# Arduino_Core.net
KiCad netlist of a schematic drawn in Altium Designer
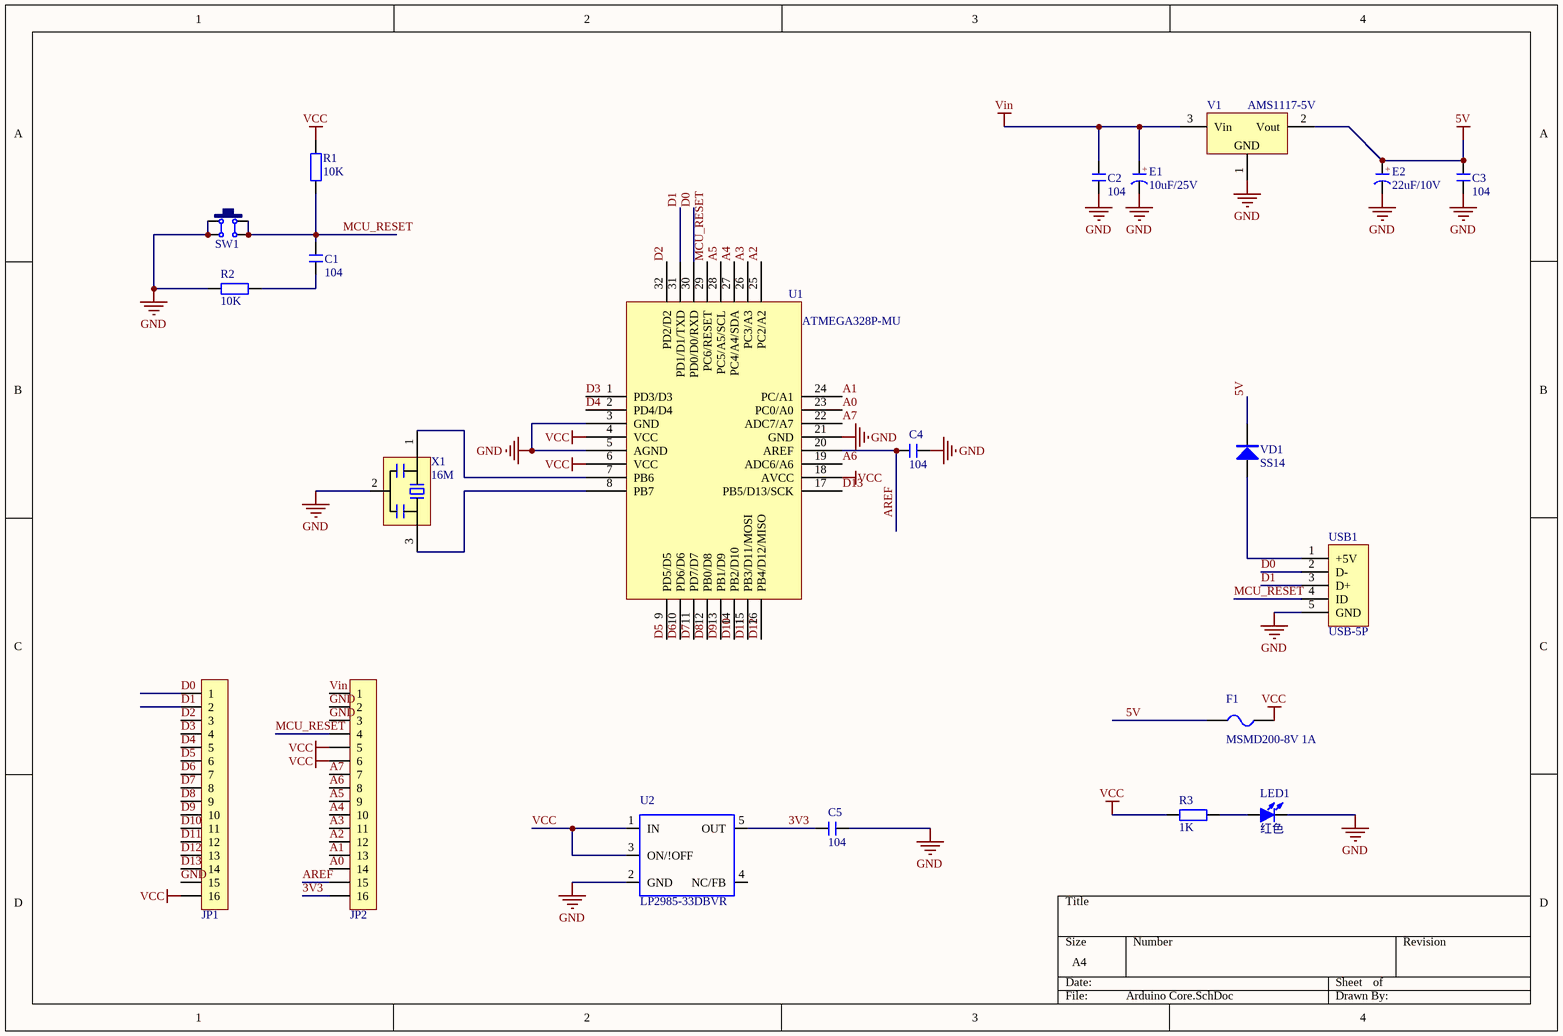
[diagram p0: Arduino Core.SchDoc]

(export (version "E")
  (design (tool "Eeschema 10.0.6"))
  (components
    (comp (ref "C1")
      (value "104")
      (footprint "C 0603")
      (description "无极性贴片电容")
      (fields (field (name "版权归属") "源创客"))
      (libsource (lib "电阻-电容-电感") (part "C"))
    )
    (comp (ref "C2")
      (value "104")
      (footprint "C 0603")
      (description "无极性贴片电容")
      (fields (field (name "版权归属") "源创客"))
      (libsource (lib "电阻-电容-电感") (part "C"))
    )
    (comp (ref "C3")
      (value "104")
      (footprint "C 0603")
      (description "无极性贴片电容")
      (fields (field (name "版权归属") "源创客"))
      (libsource (lib "电阻-电容-电感") (part "C"))
    )
    (comp (ref "C4")
      (value "104")
      (footprint "C 0603")
      (description "无极性贴片电容")
      (fields (field (name "版权归属") "源创客"))
      (libsource (lib "电阻-电容-电感") (part "C"))
    )
    (comp (ref "C5")
      (value "104")
      (footprint "C 0603")
      (description "无极性贴片电容")
      (fields (field (name "版权归属") "源创客"))
      (libsource (lib "电阻-电容-电感") (part "C"))
    )
    (comp (ref "E1")
      (value "10uF/25V")
      (footprint "CD A(3216)")
      (description "贴片钽电容")
      (fields (field (name "版权归属") "源创客"))
      (libsource (lib "电阻-电容-电感") (part "C-CD"))
    )
    (comp (ref "E2")
      (value "22uF/10V")
      (footprint "CD A(3216)")
      (description "贴片钽电容")
      (fields (field (name "版权归属") "源创客"))
      (libsource (lib "电阻-电容-电感") (part "C-CD"))
    )
    (comp (ref "F1")
      (value "MSMD200-8V 1A")
      (footprint "FU 1812")
      (description "贴片保险丝")
      (fields (field (name "版权归属") "源创客"))
      (libsource (lib "保险丝-晶振") (part "FU"))
    )
    (comp (ref "JP1")
      (value "HDR-1X16")
      (footprint "HDR-1X16")
      (description "16P接插件")
      (fields (field (name "版权归属") "源创客"))
      (libsource (lib "接插件") (part "Header 16"))
    )
    (comp (ref "JP2")
      (value "HDR-1X16")
      (footprint "HDR-1X16")
      (description "16P接插件")
      (fields (field (name "版权归属") "源创客"))
      (libsource (lib "接插件") (part "Header 16"))
    )
    (comp (ref "LED1")
      (value "红色")
      (footprint "LED 0603B")
      (description "贴片LED")
      (fields (field (name "版权归属") "源创客"))
      (libsource (lib "LED") (part "LED-SMD"))
    )
    (comp (ref "R1")
      (value "10K")
      (footprint "R 0603")
      (description "贴片电阻")
      (fields (field (name "版权归属") "源创客"))
      (libsource (lib "电阻-电容-电感") (part "R"))
    )
    (comp (ref "R2")
      (value "10K")
      (footprint "R 0603")
      (description "贴片电阻")
      (fields (field (name "版权归属") "源创客"))
      (libsource (lib "电阻-电容-电感") (part "R"))
    )
    (comp (ref "R3")
      (value "1K")
      (footprint "R 0603")
      (description "贴片电阻")
      (fields (field (name "版权归属") "源创客"))
      (libsource (lib "电阻-电容-电感") (part "R"))
    )
    (comp (ref "SW1")
      (value "4x4x1.5")
      (footprint "TS4x4x1.5")
      (description "防水轻触开关")
      (fields (field (name "版权归属") "源创客"))
      (libsource (lib "5.1   - 按键-开关") (part "TS-030"))
    )
    (comp (ref "U1")
      (value "ATMEGA328P-MU")
      (footprint "LQFP32 7X7_L")
      (description "AVR单片机")
      (fields (field (name "版权归属") "源创客"))
      (libsource (lib "Atmel系列单片机") (part "ATMEGA328P"))
    )
    (comp (ref "U2")
      (value "LP2985-33DBVR")
      (footprint "SOT23-5L")
      (libsource (lib "*") (part "LP2985-XXDBVR33"))
    )
    (comp (ref "USB1")
      (value "USB-5P")
      (footprint "USB-MICRO_D")
      (description "微型USB母座")
      (fields (field (name "版权归属") "源创客"))
      (libsource (lib "接口类") (part "USB-5P"))
    )
    (comp (ref "V1")
      (value "AMS1117-5V")
      (footprint "SOT223_N")
      (description "三端稳压芯片")
      (fields (field (name "版权归属") "源创客"))
      (libsource (lib "IC芯片") (part "AMS1117"))
    )
    (comp (ref "VD1")
      (value "SS14")
      (footprint "SMA")
      (description "肖特基二极管")
      (fields (field (name "版权归属") "源创客"))
      (libsource (lib "二极管-整流桥") (part "SS14"))
    )
    (comp (ref "X1")
      (value "16M")
      (footprint "T-3213")
      (description "3脚晶振")
      (fields (field (name "版权归属") "源创客"))
      (libsource (lib "保险丝-晶振") (part "XTAL-3"))
    )
  )
  (nets
    (net (code "1") (name "/3V3") (class "Default")
      (node (ref "C5") (pin "1") (pinfunction "1_1") (pintype "passive"))
      (node (ref "JP2") (pin "16") (pinfunction "16_16") (pintype "passive"))
      (node (ref "U2") (pin "5") (pinfunction "OUT_5") (pintype "passive"))
    )
    (net (code "2") (name "/A0") (class "Default")
      (node (ref "JP2") (pin "14") (pinfunction "14_14") (pintype "passive"))
      (node (ref "U1") (pin "23") (pinfunction "PC0/A0_23") (pintype "passive"))
    )
    (net (code "3") (name "/A1") (class "Default")
      (node (ref "JP2") (pin "13") (pinfunction "13_13") (pintype "passive"))
      (node (ref "U1") (pin "24") (pinfunction "PC/A1_24") (pintype "passive"))
    )
    (net (code "4") (name "/A2") (class "Default")
      (node (ref "JP2") (pin "12") (pinfunction "12_12") (pintype "passive"))
      (node (ref "U1") (pin "25") (pinfunction "PC2/A2_25") (pintype "passive"))
    )
    (net (code "5") (name "/A3") (class "Default")
      (node (ref "JP2") (pin "11") (pinfunction "11_11") (pintype "passive"))
      (node (ref "U1") (pin "26") (pinfunction "PC3/A3_26") (pintype "passive"))
    )
    (net (code "6") (name "/A4") (class "Default")
      (node (ref "JP2") (pin "10") (pinfunction "10_10") (pintype "passive"))
      (node (ref "U1") (pin "27") (pinfunction "PC4/A4/SDA_27") (pintype "passive"))
    )
    (net (code "7") (name "/A5") (class "Default")
      (node (ref "JP2") (pin "9") (pinfunction "9_9") (pintype "passive"))
      (node (ref "U1") (pin "28") (pinfunction "PC5/A5/SCL_28") (pintype "passive"))
    )
    (net (code "8") (name "/A6") (class "Default")
      (node (ref "JP2") (pin "8") (pinfunction "8_8") (pintype "passive"))
      (node (ref "U1") (pin "19") (pinfunction "ADC6/A6_19") (pintype "passive"))
    )
    (net (code "9") (name "/A7") (class "Default")
      (node (ref "JP2") (pin "7") (pinfunction "7_7") (pintype "passive"))
      (node (ref "U1") (pin "22") (pinfunction "ADC7/A7_22") (pintype "passive"))
    )
    (net (code "10") (name "/AREF") (class "Default")
      (node (ref "C4") (pin "1") (pinfunction "1_1") (pintype "passive"))
      (node (ref "JP2") (pin "15") (pinfunction "15_15") (pintype "passive"))
      (node (ref "U1") (pin "20") (pinfunction "AREF_20") (pintype "passive"))
    )
    (net (code "11") (name "/D0") (class "Default")
      (node (ref "JP1") (pin "1") (pinfunction "1_1") (pintype "passive"))
      (node (ref "U1") (pin "30") (pinfunction "PD0/D0/RXD_30") (pintype "passive"))
      (node (ref "USB1") (pin "2") (pinfunction "D-_2") (pintype "passive"))
    )
    (net (code "12") (name "/D1") (class "Default")
      (node (ref "JP1") (pin "2") (pinfunction "2_2") (pintype "passive"))
      (node (ref "U1") (pin "31") (pinfunction "PD1/D1/TXD_31") (pintype "passive"))
      (node (ref "USB1") (pin "3") (pinfunction "D+_3") (pintype "passive"))
    )
    (net (code "13") (name "/D2") (class "Default")
      (node (ref "JP1") (pin "3") (pinfunction "3_3") (pintype "passive"))
      (node (ref "U1") (pin "32") (pinfunction "PD2/D2_32") (pintype "passive"))
    )
    (net (code "14") (name "/D3") (class "Default")
      (node (ref "JP1") (pin "4") (pinfunction "4_4") (pintype "passive"))
      (node (ref "U1") (pin "1") (pinfunction "PD3/D3_1") (pintype "passive"))
    )
    (net (code "15") (name "/D4") (class "Default")
      (node (ref "JP1") (pin "5") (pinfunction "5_5") (pintype "passive"))
      (node (ref "U1") (pin "2") (pinfunction "PD4/D4_2") (pintype "passive"))
    )
    (net (code "16") (name "/D5") (class "Default")
      (node (ref "JP1") (pin "6") (pinfunction "6_6") (pintype "passive"))
      (node (ref "U1") (pin "9") (pinfunction "PD5/D5_9") (pintype "passive"))
    )
    (net (code "17") (name "/D6") (class "Default")
      (node (ref "JP1") (pin "7") (pinfunction "7_7") (pintype "passive"))
      (node (ref "U1") (pin "10") (pinfunction "PD6/D6_10") (pintype "passive"))
    )
    (net (code "18") (name "/D7") (class "Default")
      (node (ref "JP1") (pin "8") (pinfunction "8_8") (pintype "passive"))
      (node (ref "U1") (pin "11") (pinfunction "PD7/D7_11") (pintype "passive"))
    )
    (net (code "19") (name "/D8") (class "Default")
      (node (ref "JP1") (pin "9") (pinfunction "9_9") (pintype "passive"))
      (node (ref "U1") (pin "12") (pinfunction "PB0/D8_12") (pintype "passive"))
    )
    (net (code "20") (name "/D9") (class "Default")
      (node (ref "JP1") (pin "10") (pinfunction "10_10") (pintype "passive"))
      (node (ref "U1") (pin "13") (pinfunction "PB1/D9_13") (pintype "passive"))
    )
    (net (code "21") (name "/D10") (class "Default")
      (node (ref "JP1") (pin "11") (pinfunction "11_11") (pintype "passive"))
      (node (ref "U1") (pin "14") (pinfunction "PB2/D10_14") (pintype "passive"))
    )
    (net (code "22") (name "/D11") (class "Default")
      (node (ref "JP1") (pin "12") (pinfunction "12_12") (pintype "passive"))
      (node (ref "U1") (pin "15") (pinfunction "PB3/D11/MOSI_15") (pintype "passive"))
    )
    (net (code "23") (name "/D12") (class "Default")
      (node (ref "JP1") (pin "13") (pinfunction "13_13") (pintype "passive"))
      (node (ref "U1") (pin "16") (pinfunction "PB4/D12/MISO_16") (pintype "passive"))
    )
    (net (code "24") (name "/D13") (class "Default")
      (node (ref "JP1") (pin "14") (pinfunction "14_14") (pintype "passive"))
      (node (ref "U1") (pin "17") (pinfunction "PB5/D13/SCK_17") (pintype "passive"))
    )
    (net (code "25") (name "/MCU_RESET") (class "Default")
      (node (ref "C1") (pin "2") (pinfunction "2_2") (pintype "passive"))
      (node (ref "JP2") (pin "4") (pinfunction "4_4") (pintype "passive"))
      (node (ref "R1") (pin "2") (pinfunction "2_2") (pintype "passive"))
      (node (ref "SW1") (pin "2") (pinfunction "2_2") (pintype "passive"))
      (node (ref "SW1") (pin "3") (pinfunction "3_3") (pintype "passive"))
      (node (ref "U1") (pin "29") (pinfunction "PC6/RESET_29") (pintype "passive"))
      (node (ref "USB1") (pin "4") (pinfunction "ID_4") (pintype "passive"))
    )
    (net (code "26") (name "5V") (class "Default")
      (node (ref "C3") (pin "2") (pinfunction "2_2") (pintype "passive"))
      (node (ref "E2") (pin "1") (pinfunction "A_1") (pintype "passive"))
      (node (ref "F1") (pin "1") (pinfunction "1_1") (pintype "passive"))
      (node (ref "V1") (pin "2") (pinfunction "Vout_2") (pintype "passive"))
      (node (ref "VD1") (pin "2") (pinfunction "K_2") (pintype "passive"))
    )
    (net (code "27") (name "GND") (class "Default")
      (node (ref "C2") (pin "1") (pinfunction "1_1") (pintype "passive"))
      (node (ref "C3") (pin "1") (pinfunction "1_1") (pintype "passive"))
      (node (ref "C4") (pin "2") (pinfunction "2_2") (pintype "passive"))
      (node (ref "C5") (pin "2") (pinfunction "2_2") (pintype "passive"))
      (node (ref "E1") (pin "2") (pinfunction "K_2") (pintype "passive"))
      (node (ref "E2") (pin "2") (pinfunction "K_2") (pintype "passive"))
      (node (ref "JP1") (pin "15") (pinfunction "15_15") (pintype "passive"))
      (node (ref "JP2") (pin "2") (pinfunction "2_2") (pintype "passive"))
      (node (ref "JP2") (pin "3") (pinfunction "3_3") (pintype "passive"))
      (node (ref "LED1") (pin "2") (pinfunction "K_2") (pintype "passive"))
      (node (ref "R2") (pin "1") (pinfunction "1_1") (pintype "passive"))
      (node (ref "SW1") (pin "1") (pinfunction "1_1") (pintype "passive"))
      (node (ref "SW1") (pin "4") (pinfunction "4_4") (pintype "passive"))
      (node (ref "U1") (pin "21") (pinfunction "GND_21") (pintype "passive"))
      (node (ref "U1") (pin "3") (pinfunction "GND_3") (pintype "passive"))
      (node (ref "U1") (pin "5") (pinfunction "AGND_5") (pintype "passive"))
      (node (ref "U2") (pin "2") (pinfunction "GND_2") (pintype "passive"))
      (node (ref "USB1") (pin "5") (pinfunction "GND_5") (pintype "passive"))
      (node (ref "V1") (pin "1") (pinfunction "GND_1") (pintype "passive"))
      (node (ref "X1") (pin "2") (pinfunction "2_2") (pintype "passive"))
    )
    (net (code "28") (name "Net-(C1-Pad1)") (class "Default")
      (node (ref "C1") (pin "1") (pinfunction "1_1") (pintype "passive"))
      (node (ref "R2") (pin "2") (pinfunction "2_2") (pintype "passive"))
    )
    (net (code "29") (name "Net-(LED1-A)") (class "Default")
      (node (ref "LED1") (pin "1") (pinfunction "A_1") (pintype "passive"))
      (node (ref "R3") (pin "2") (pinfunction "2_2") (pintype "passive"))
    )
    (net (code "30") (name "Net-(U1-PB6)") (class "Default")
      (node (ref "U1") (pin "7") (pinfunction "PB6_7") (pintype "passive"))
      (node (ref "X1") (pin "1") (pinfunction "1_1") (pintype "passive"))
    )
    (net (code "31") (name "Net-(U1-PB7)") (class "Default")
      (node (ref "U1") (pin "8") (pinfunction "PB7_8") (pintype "passive"))
      (node (ref "X1") (pin "3") (pinfunction "3_3") (pintype "passive"))
    )
    (net (code "32") (name "Net-(USB1-+5V)") (class "Default")
      (node (ref "USB1") (pin "1") (pinfunction "+5V_1") (pintype "passive"))
      (node (ref "VD1") (pin "1") (pinfunction "A_1") (pintype "passive"))
    )
    (net (code "33") (name "VCC") (class "Default")
      (node (ref "F1") (pin "2") (pinfunction "2_2") (pintype "passive"))
      (node (ref "JP1") (pin "16") (pinfunction "16_16") (pintype "passive"))
      (node (ref "JP2") (pin "5") (pinfunction "5_5") (pintype "passive"))
      (node (ref "JP2") (pin "6") (pinfunction "6_6") (pintype "passive"))
      (node (ref "R1") (pin "1") (pinfunction "1_1") (pintype "passive"))
      (node (ref "R3") (pin "1") (pinfunction "1_1") (pintype "passive"))
      (node (ref "U1") (pin "18") (pinfunction "AVCC_18") (pintype "passive"))
      (node (ref "U1") (pin "4") (pinfunction "VCC_4") (pintype "passive"))
      (node (ref "U1") (pin "6") (pinfunction "VCC_6") (pintype "passive"))
      (node (ref "U2") (pin "1") (pinfunction "IN_1") (pintype "passive"))
      (node (ref "U2") (pin "3") (pinfunction "ON/!OFF_3") (pintype "passive"))
    )
    (net (code "34") (name "Vin") (class "Default")
      (node (ref "C2") (pin "2") (pinfunction "2_2") (pintype "passive"))
      (node (ref "E1") (pin "1") (pinfunction "A_1") (pintype "passive"))
      (node (ref "JP2") (pin "1") (pinfunction "1_1") (pintype "passive"))
      (node (ref "V1") (pin "3") (pinfunction "Vin_3") (pintype "passive"))
    )
    (net (code "35") (name "unconnected-(U2-NC{slash}FB-Pad4)") (class "Default")
      (node (ref "U2") (pin "4") (pinfunction "NC/FB_4") (pintype "passive"))
    )
  )
)
